# ProPrj_3_3VBuck_1117_2024-12-16.net
KiCad netlist of a schematic drawn in EasyEDA Pro
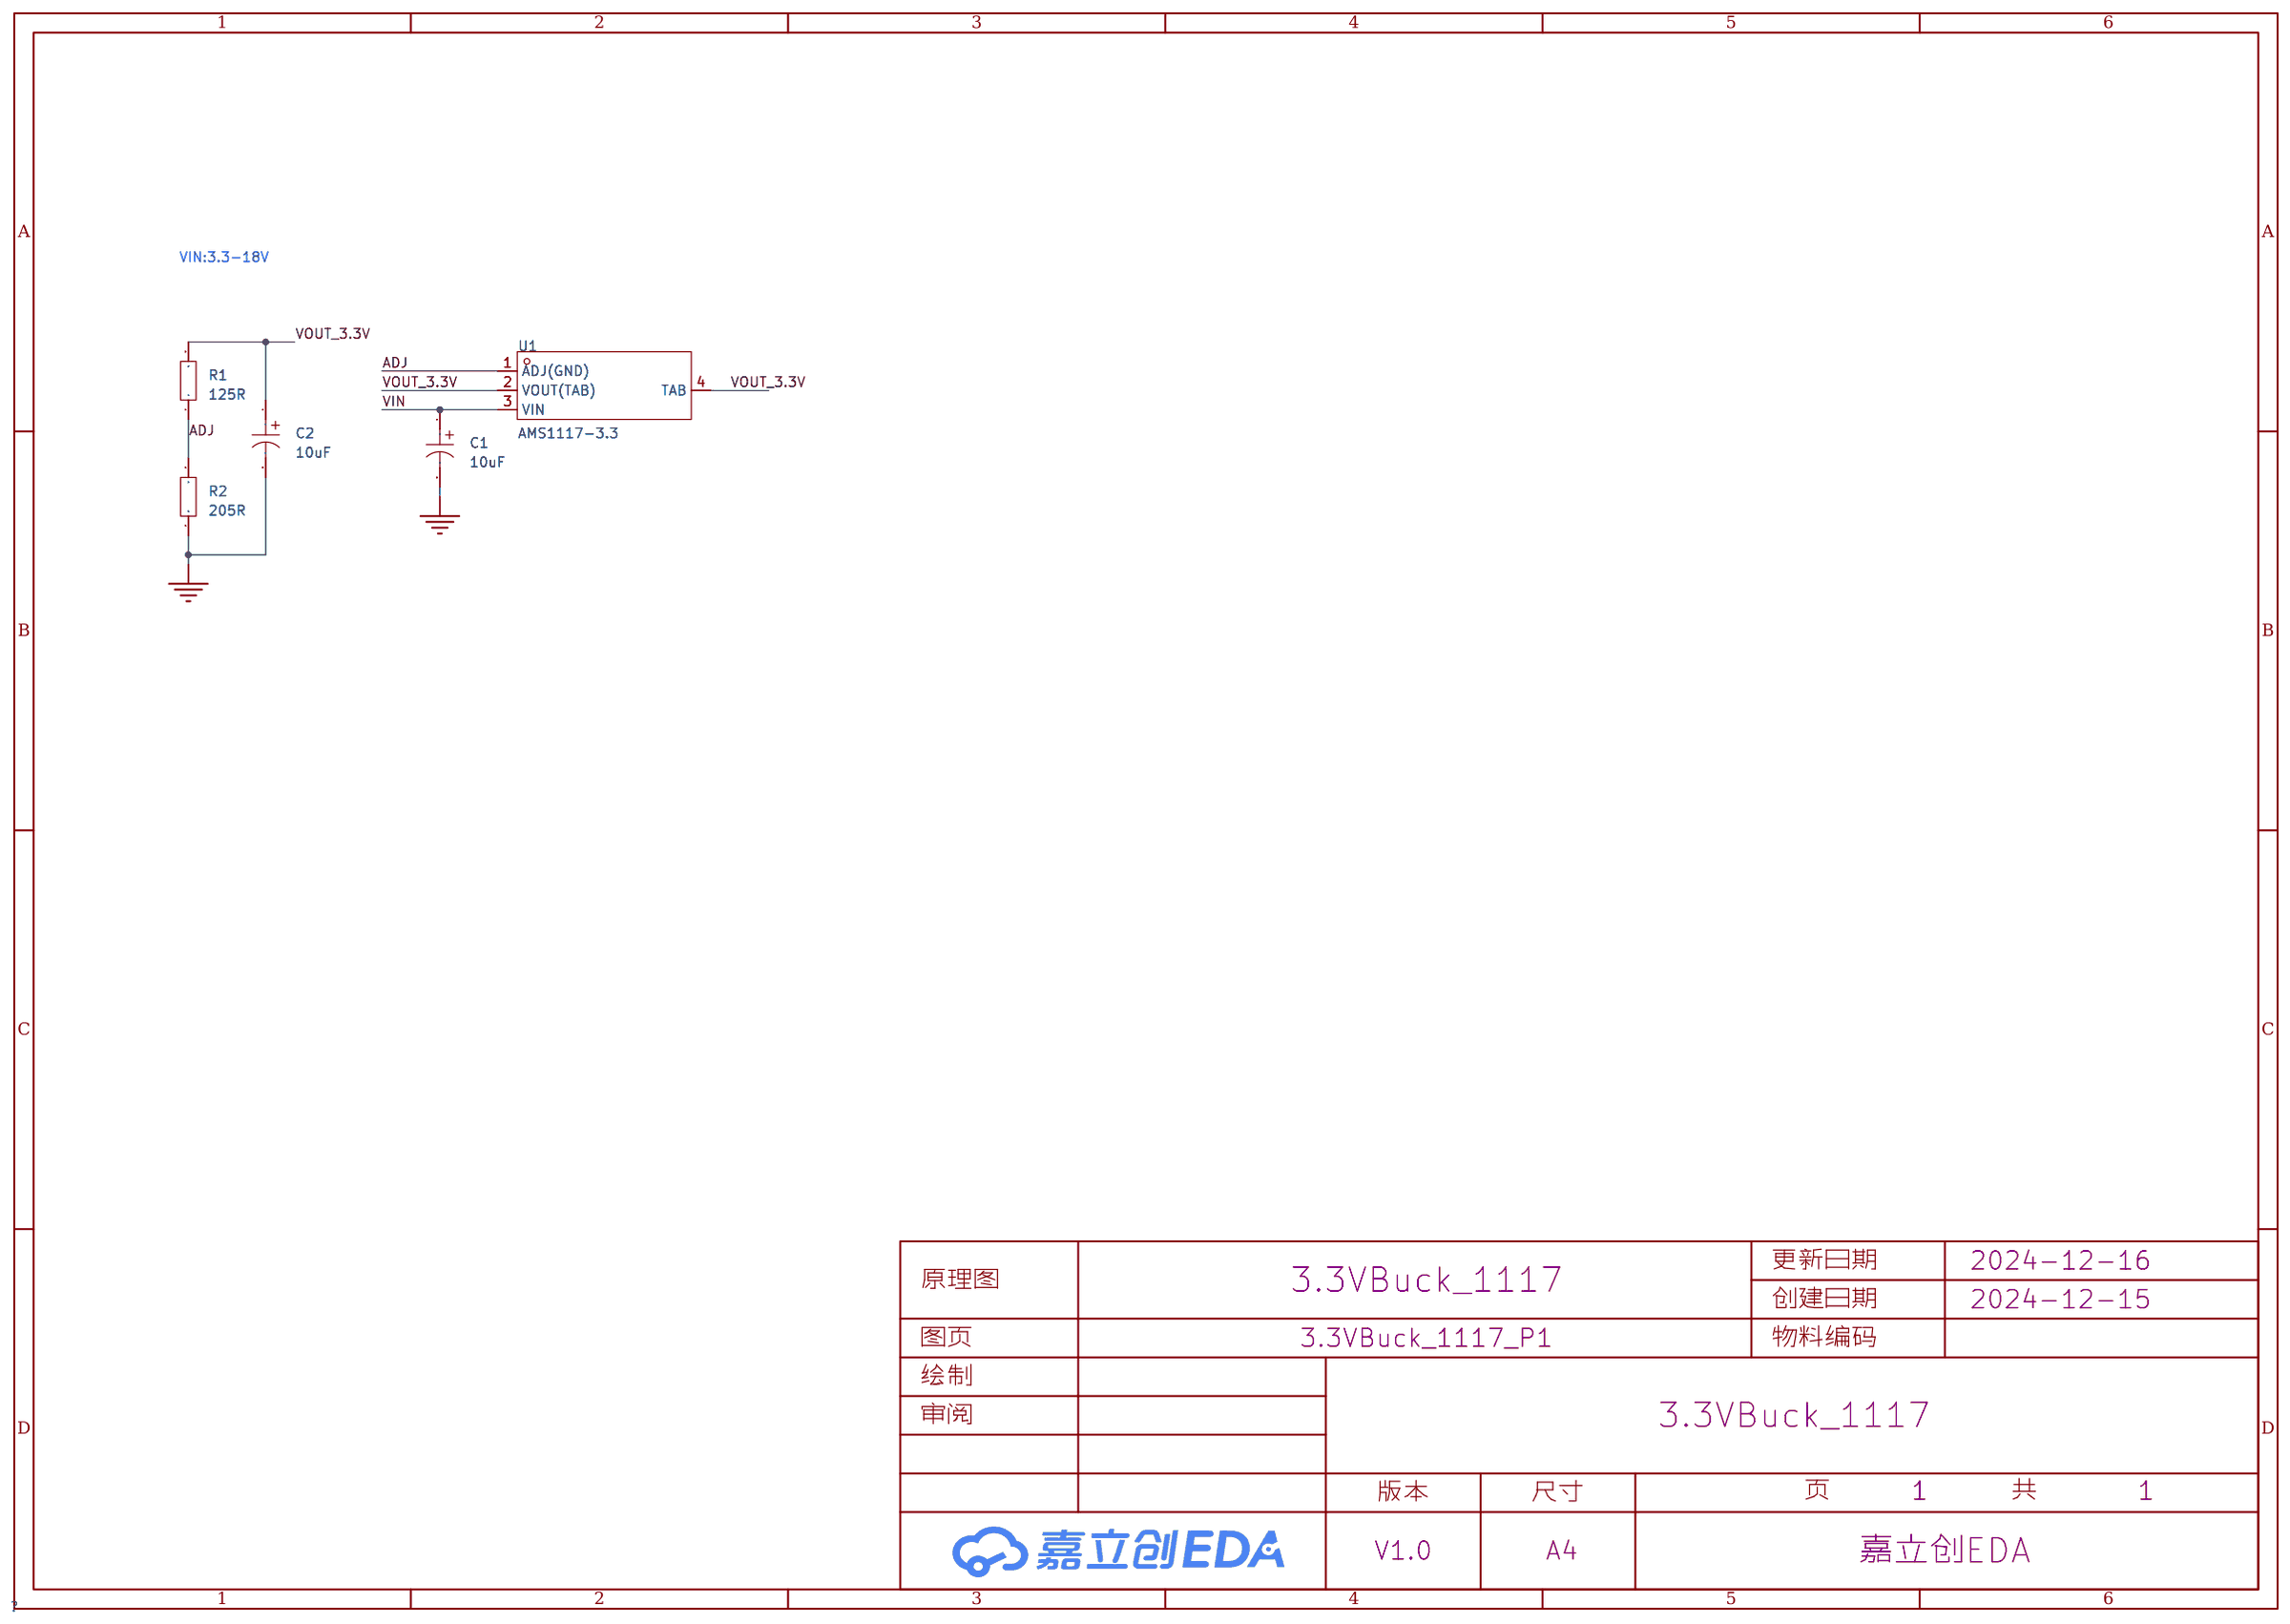
[diagram p0: schematic sheet]

(export (version "E")
  (design (tool "Eeschema 10.0.6"))
  (components
    (comp (ref "C1")
      (value "10uF")
      (footprint "easyedapro:CAP-SMD_L2.0-W1.3-FD")
      (description "容值:10uF;精度:±20%;额定电压:10V;等效串联电阻:5.9Ω@100kHz;")
      (fields (field (name "Manufacturer Part") "TMCP1A106MTRF") (field (name "Manufacturer") "VISHAY(威世)"))
      (libsource (lib "easyedapro") (part "TMCP1A106MTRF"))
    )
    (comp (ref "C2")
      (value "10uF")
      (footprint "easyedapro:CAP-SMD_L2.0-W1.3-FD")
      (description "容值:10uF;精度:±20%;额定电压:10V;等效串联电阻:5.9Ω@100kHz;")
      (fields (field (name "Manufacturer Part") "TMCP1A106MTRF") (field (name "Manufacturer") "VISHAY(威世)"))
      (libsource (lib "easyedapro") (part "TMCP1A106MTRF"))
    )
    (comp (ref "R1") (value "125R") (footprint "easyedapro:R0805") (libsource (lib "easyedapro") (part "电阻")))
    (comp (ref "R2") (value "205R") (footprint "easyedapro:R0805") (libsource (lib "easyedapro") (part "电阻")))
    (comp (ref "U1")
      (value "AMS1117-3.3")
      (footprint "easyedapro:SOT-223-4_L6.5-W3.5-P2.30-LS7.0-BR")
      (description "输出类型:固定;最大输入电压:18V;输出电压:3.3V;输出电流:1A;电源纹波抑制比(PSRR):60dB@(120Hz);输出极性:正极;")
      (fields (field (name "Manufacturer") "UMW(友台半导体)"))
      (libsource (lib "easyedapro") (part "AMS1117-3.3_C347222"))
    )
  )
  (nets
    (net (code "1") (name "/ADJ") (class "Default")
      (node (ref "R1") (pin "1") (pinfunction "1_1") (pintype "input"))
      (node (ref "R2") (pin "2") (pinfunction "2_2") (pintype "input"))
      (node (ref "U1") (pin "1") (pinfunction "ADJ(GND)_1") (pintype "unspecified"))
    )
    (net (code "2") (name "/VIN") (class "Default")
      (node (ref "C1") (pin "1") (pinfunction "1_1") (pintype "input"))
      (node (ref "U1") (pin "3") (pinfunction "VIN_3") (pintype "unspecified"))
    )
    (net (code "3") (name "/VOUT_3.3V") (class "Default")
      (node (ref "C2") (pin "1") (pinfunction "1_1") (pintype "input"))
      (node (ref "R1") (pin "2") (pinfunction "2_2") (pintype "input"))
      (node (ref "U1") (pin "2") (pinfunction "VOUT(TAB)_2") (pintype "unspecified"))
      (node (ref "U1") (pin "4") (pinfunction "TAB_4") (pintype "unspecified"))
    )
    (net (code "4") (name "GND") (class "Default")
      (node (ref "C1") (pin "2") (pinfunction "2_2") (pintype "input"))
      (node (ref "C2") (pin "2") (pinfunction "2_2") (pintype "input"))
      (node (ref "R2") (pin "1") (pinfunction "1_1") (pintype "input"))
    )
  )
)
